# gluecksrad.net
KiCad netlist of a schematic drawn in EAGLE
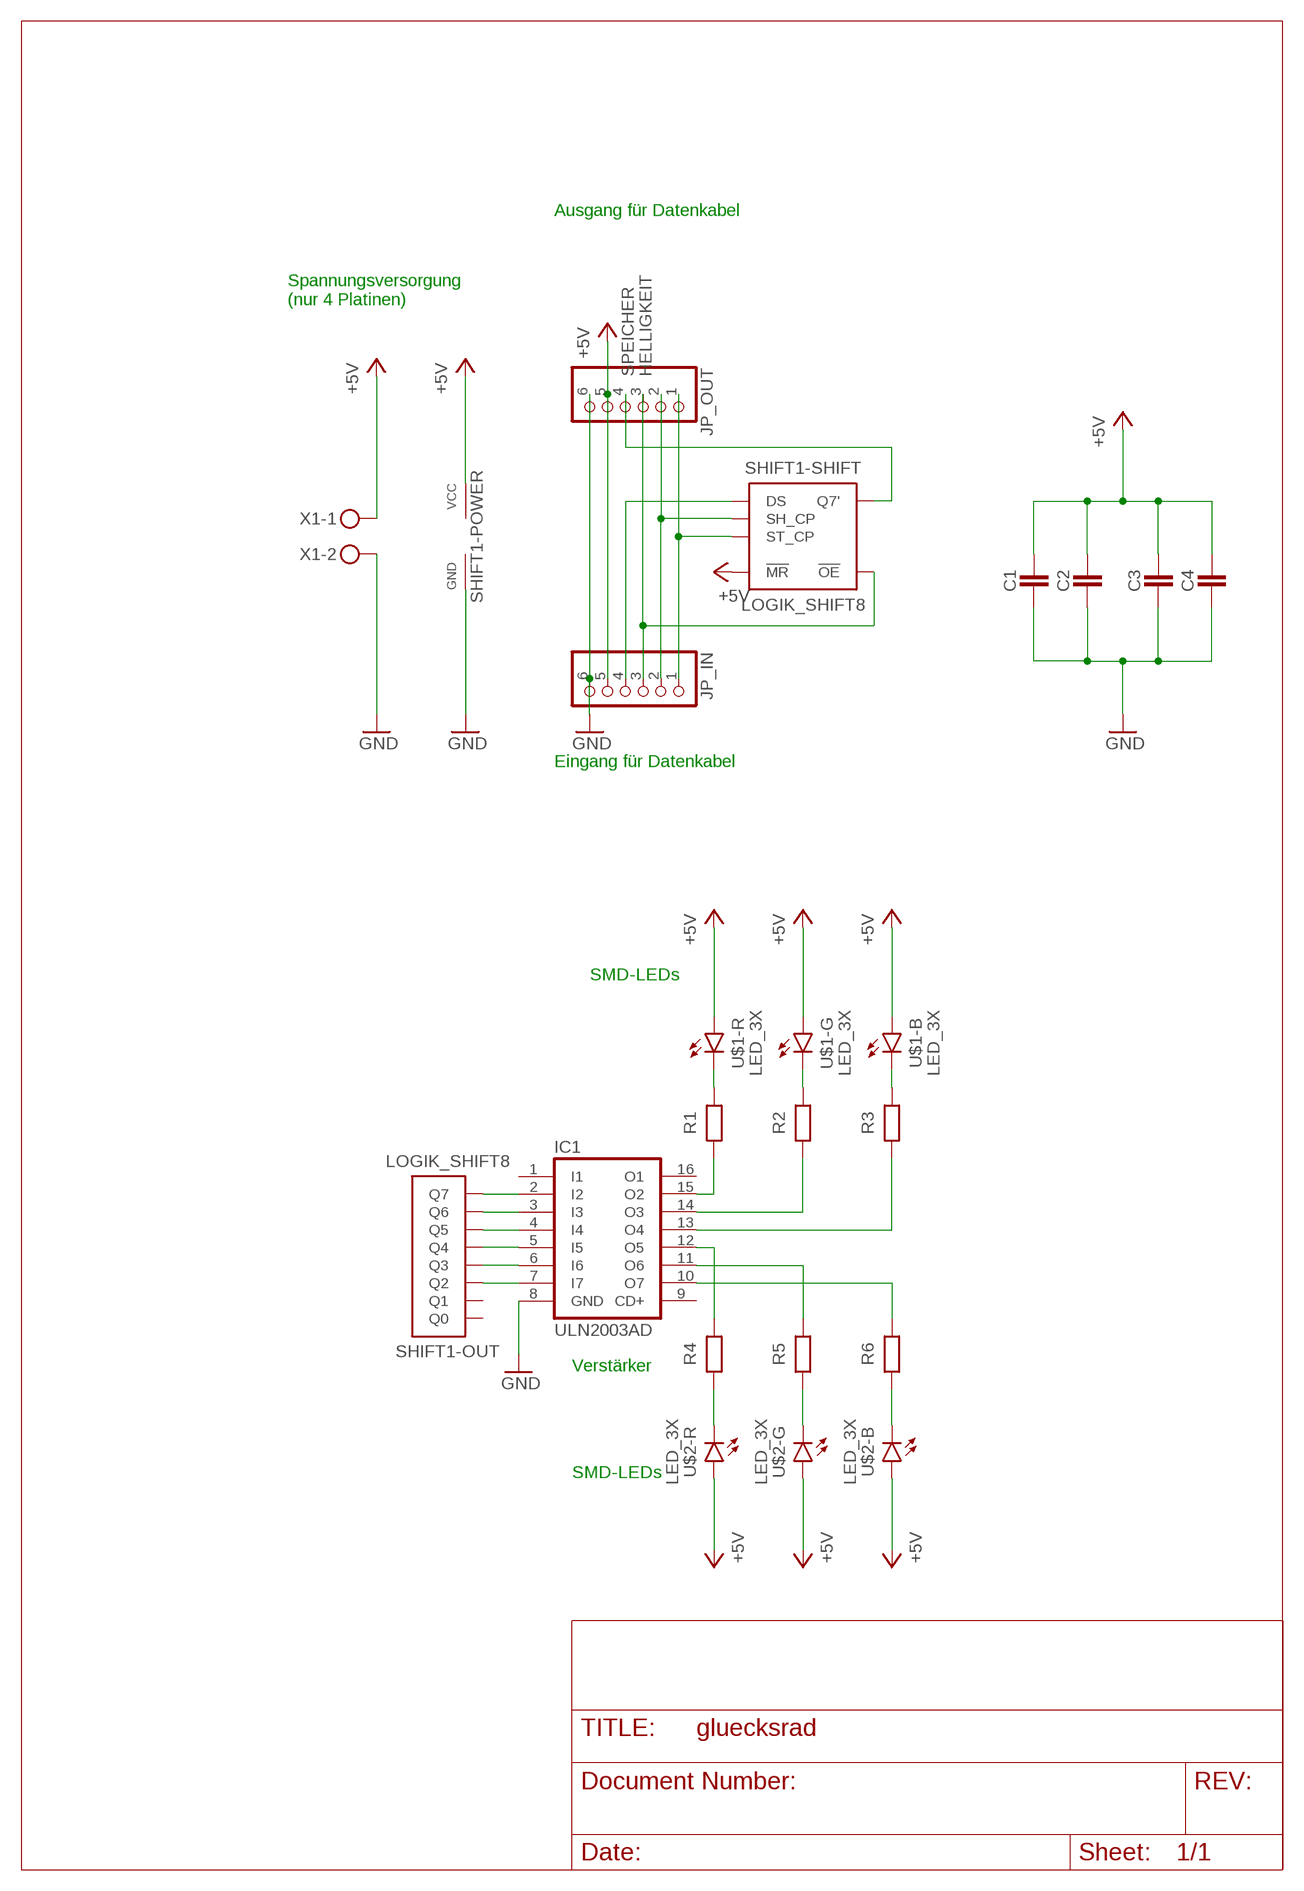
[diagram p0: schematic, sheet 1]

(export (version "E")
  (design (tool "Eeschema 10.0.6"))
  (components
    (comp (ref "C1")
      (value "CAPACITATOR-2,5MM")
      (footprint "eagle-import:C_THT_2")
      (libsource (lib "eagle-import") (part "CAPACITATOR-2,5MM"))
    )
    (comp (ref "C2")
      (value "CAPACITATOR-5MM")
      (footprint "eagle-import:C_THT_3")
      (libsource (lib "eagle-import") (part "CAPACITATOR-5MM"))
    )
    (comp (ref "C3")
      (value "CAPACITATOR-2,5MM")
      (footprint "eagle-import:C_THT_2")
      (libsource (lib "eagle-import") (part "CAPACITATOR-2,5MM"))
    )
    (comp (ref "C4")
      (value "CAPACITATOR-2,5MM")
      (footprint "eagle-import:C_THT_2")
      (libsource (lib "eagle-import") (part "CAPACITATOR-2,5MM"))
    )
    (comp (ref "IC1")
      (value "ULN2003AD")
      (footprint "eagle-import:SO16")
      (libsource (lib "eagle-import") (part "ULN2003AD"))
    )
    (comp (ref "JP_IN")
      (value "PINHD-1X6/90")
      (footprint "eagle-import:1X06_90")
      (libsource (lib "eagle-import") (part "PINHD-1X6/90"))
    )
    (comp (ref "JP_OUT")
      (value "PINHD-1X6/90")
      (footprint "eagle-import:1X06_90")
      (libsource (lib "eagle-import") (part "PINHD-1X6/90"))
    )
    (comp (ref "R1")
      (value "RESISTOR-10MM")
      (footprint "eagle-import:R_THT_4")
      (libsource (lib "eagle-import") (part "RESISTOR-10MM"))
    )
    (comp (ref "R2")
      (value "RESISTOR-10MM")
      (footprint "eagle-import:R_THT_4")
      (libsource (lib "eagle-import") (part "RESISTOR-10MM"))
    )
    (comp (ref "R3")
      (value "RESISTOR-10MM")
      (footprint "eagle-import:R_THT_4")
      (libsource (lib "eagle-import") (part "RESISTOR-10MM"))
    )
    (comp (ref "R4")
      (value "RESISTOR-10MM")
      (footprint "eagle-import:R_THT_4")
      (libsource (lib "eagle-import") (part "RESISTOR-10MM"))
    )
    (comp (ref "R5")
      (value "RESISTOR-10MM")
      (footprint "eagle-import:R_THT_4")
      (libsource (lib "eagle-import") (part "RESISTOR-10MM"))
    )
    (comp (ref "R6")
      (value "RESISTOR-10MM")
      (footprint "eagle-import:R_THT_4")
      (libsource (lib "eagle-import") (part "RESISTOR-10MM"))
    )
    (comp (ref "SHIFT1")
      (value "LOGIK_SHIFT8")
      (footprint "eagle-import:IC_SOIC16")
      (libsource (lib "eagle-import") (part "LOGIK_SHIFT8"))
    )
    (comp (ref "U$1")
      (value "LED_3X")
      (footprint "eagle-import:LED_TOP_PLCC6")
      (libsource (lib "eagle-import") (part "LED_3X"))
    )
    (comp (ref "U$2")
      (value "LED_3X")
      (footprint "eagle-import:LED_TOP_PLCC6")
      (libsource (lib "eagle-import") (part "LED_3X"))
    )
    (comp (ref "X1")
      (value "STECKER_SPG_2")
      (footprint "eagle-import:STECKER_SPG_2")
      (libsource (lib "eagle-import") (part "STECKER_SPG_2"))
    )
  )
  (nets
    (net (code "1") (name "+5V") (class "Default")
      (node (ref "C1") (pin "1") (pinfunction "1_1") (pintype "passive"))
      (node (ref "C2") (pin "1") (pinfunction "1_1") (pintype "passive"))
      (node (ref "C3") (pin "1") (pinfunction "1_1") (pintype "passive"))
      (node (ref "C4") (pin "1") (pinfunction "1_1") (pintype "passive"))
      (node (ref "JP_IN") (pin "5") (pinfunction "5_5") (pintype "passive"))
      (node (ref "JP_OUT") (pin "5") (pinfunction "5_5") (pintype "passive"))
      (node (ref "SHIFT1") (pin "P$10") (pinfunction "~{MR}_P$10") (pintype "input"))
      (node (ref "SHIFT1") (pin "P$16") (pinfunction "VCC_P$16") (pintype "power_in"))
      (node (ref "U$1") (pin "1") (pinfunction "A_1") (pintype "passive"))
      (node (ref "U$1") (pin "3") (pinfunction "A_3") (pintype "passive"))
      (node (ref "U$1") (pin "4") (pinfunction "A_4") (pintype "passive"))
      (node (ref "U$2") (pin "1") (pinfunction "A_1") (pintype "passive"))
      (node (ref "U$2") (pin "3") (pinfunction "A_3") (pintype "passive"))
      (node (ref "U$2") (pin "4") (pinfunction "A_4") (pintype "passive"))
      (node (ref "X1") (pin "1") (pinfunction "KL_1") (pintype "passive"))
    )
    (net (code "2") (name "/HELLIGKEIT") (class "Default")
      (node (ref "JP_IN") (pin "3") (pinfunction "3_3") (pintype "passive"))
      (node (ref "JP_OUT") (pin "3") (pinfunction "3_3") (pintype "passive"))
      (node (ref "SHIFT1") (pin "P$13") (pinfunction "~{OE}_P$13") (pintype "input"))
    )
    (net (code "3") (name "/SPEICHER") (class "Default")
      (node (ref "JP_IN") (pin "1") (pinfunction "1_1") (pintype "passive"))
      (node (ref "JP_OUT") (pin "1") (pinfunction "1_1") (pintype "passive"))
      (node (ref "SHIFT1") (pin "P$12") (pinfunction "ST_CP_P$12") (pintype "input"))
    )
    (net (code "4") (name "GND") (class "Default")
      (node (ref "C1") (pin "2") (pinfunction "2_2") (pintype "passive"))
      (node (ref "C2") (pin "2") (pinfunction "2_2") (pintype "passive"))
      (node (ref "C3") (pin "2") (pinfunction "2_2") (pintype "passive"))
      (node (ref "C4") (pin "2") (pinfunction "2_2") (pintype "passive"))
      (node (ref "IC1") (pin "8") (pinfunction "GND_8") (pintype "power_in"))
      (node (ref "JP_IN") (pin "6") (pinfunction "6_6") (pintype "passive"))
      (node (ref "JP_OUT") (pin "6") (pinfunction "6_6") (pintype "passive"))
      (node (ref "SHIFT1") (pin "P$8") (pinfunction "GND_P$8") (pintype "power_in"))
      (node (ref "X1") (pin "2") (pinfunction "KL_2") (pintype "passive"))
    )
    (net (code "5") (name "Net-(IC1-I2)") (class "Default")
      (node (ref "IC1") (pin "2") (pinfunction "I2_2") (pintype "input"))
      (node (ref "SHIFT1") (pin "P$7") (pinfunction "Q7_P$7") (pintype "output"))
    )
    (net (code "6") (name "Net-(IC1-I3)") (class "Default")
      (node (ref "IC1") (pin "3") (pinfunction "I3_3") (pintype "input"))
      (node (ref "SHIFT1") (pin "P$6") (pinfunction "Q6_P$6") (pintype "output"))
    )
    (net (code "7") (name "Net-(IC1-I4)") (class "Default")
      (node (ref "IC1") (pin "4") (pinfunction "I4_4") (pintype "input"))
      (node (ref "SHIFT1") (pin "P$5") (pinfunction "Q5_P$5") (pintype "output"))
    )
    (net (code "8") (name "Net-(IC1-I5)") (class "Default")
      (node (ref "IC1") (pin "5") (pinfunction "I5_5") (pintype "input"))
      (node (ref "SHIFT1") (pin "P$4") (pinfunction "Q4_P$4") (pintype "output"))
    )
    (net (code "9") (name "Net-(IC1-I6)") (class "Default")
      (node (ref "IC1") (pin "6") (pinfunction "I6_6") (pintype "input"))
      (node (ref "SHIFT1") (pin "P$3") (pinfunction "Q3_P$3") (pintype "output"))
    )
    (net (code "10") (name "Net-(IC1-I7)") (class "Default")
      (node (ref "IC1") (pin "7") (pinfunction "I7_7") (pintype "input"))
      (node (ref "SHIFT1") (pin "P$2") (pinfunction "Q2_P$2") (pintype "output"))
    )
    (net (code "11") (name "Net-(IC1-O2)") (class "Default")
      (node (ref "IC1") (pin "15") (pinfunction "O2_15") (pintype "open_collector"))
      (node (ref "R1") (pin "2") (pinfunction "P2_2") (pintype "passive"))
    )
    (net (code "12") (name "Net-(IC1-O3)") (class "Default")
      (node (ref "IC1") (pin "14") (pinfunction "O3_14") (pintype "open_collector"))
      (node (ref "R2") (pin "2") (pinfunction "P2_2") (pintype "passive"))
    )
    (net (code "13") (name "Net-(IC1-O4)") (class "Default")
      (node (ref "IC1") (pin "13") (pinfunction "O4_13") (pintype "open_collector"))
      (node (ref "R3") (pin "2") (pinfunction "P2_2") (pintype "passive"))
    )
    (net (code "14") (name "Net-(IC1-O5)") (class "Default")
      (node (ref "IC1") (pin "12") (pinfunction "O5_12") (pintype "open_collector"))
      (node (ref "R4") (pin "1") (pinfunction "P1_1") (pintype "passive"))
    )
    (net (code "15") (name "Net-(IC1-O6)") (class "Default")
      (node (ref "IC1") (pin "11") (pinfunction "O6_11") (pintype "open_collector"))
      (node (ref "R5") (pin "1") (pinfunction "P1_1") (pintype "passive"))
    )
    (net (code "16") (name "Net-(IC1-O7)") (class "Default")
      (node (ref "IC1") (pin "10") (pinfunction "O7_10") (pintype "open_collector"))
      (node (ref "R6") (pin "1") (pinfunction "P1_1") (pintype "passive"))
    )
    (net (code "17") (name "Net-(R1-P1)") (class "Default")
      (node (ref "R1") (pin "1") (pinfunction "P1_1") (pintype "passive"))
      (node (ref "U$1") (pin "6") (pinfunction "C_6") (pintype "passive"))
    )
    (net (code "18") (name "Net-(R2-P1)") (class "Default")
      (node (ref "R2") (pin "1") (pinfunction "P1_1") (pintype "passive"))
      (node (ref "U$1") (pin "2") (pinfunction "C_2") (pintype "passive"))
    )
    (net (code "19") (name "Net-(R3-P1)") (class "Default")
      (node (ref "R3") (pin "1") (pinfunction "P1_1") (pintype "passive"))
      (node (ref "U$1") (pin "5") (pinfunction "C_5") (pintype "passive"))
    )
    (net (code "20") (name "Net-(R4-P2)") (class "Default")
      (node (ref "R4") (pin "2") (pinfunction "P2_2") (pintype "passive"))
      (node (ref "U$2") (pin "6") (pinfunction "C_6") (pintype "passive"))
    )
    (net (code "21") (name "Net-(R5-P2)") (class "Default")
      (node (ref "R5") (pin "2") (pinfunction "P2_2") (pintype "passive"))
      (node (ref "U$2") (pin "2") (pinfunction "C_2") (pintype "passive"))
    )
    (net (code "22") (name "Net-(R6-P2)") (class "Default")
      (node (ref "R6") (pin "2") (pinfunction "P2_2") (pintype "passive"))
      (node (ref "U$2") (pin "5") (pinfunction "C_5") (pintype "passive"))
    )
    (net (code "23") (name "Net-(SHIFT1C-DS)") (class "Default")
      (node (ref "JP_IN") (pin "4") (pinfunction "4_4") (pintype "passive"))
      (node (ref "SHIFT1") (pin "P$14") (pinfunction "DS_P$14") (pintype "input"))
    )
    (net (code "24") (name "Net-(SHIFT1C-Q7')") (class "Default")
      (node (ref "JP_OUT") (pin "4") (pinfunction "4_4") (pintype "passive"))
      (node (ref "SHIFT1") (pin "P$9") (pinfunction "Q7'_P$9") (pintype "output"))
    )
    (net (code "25") (name "Net-(SHIFT1C-SH_CP)") (class "Default")
      (node (ref "JP_IN") (pin "2") (pinfunction "2_2") (pintype "passive"))
      (node (ref "JP_OUT") (pin "2") (pinfunction "2_2") (pintype "passive"))
      (node (ref "SHIFT1") (pin "P$11") (pinfunction "SH_CP_P$11") (pintype "input"))
    )
    (net (code "26") (name "unconnected-(IC1-CD+-Pad9)") (class "Default")
      (node (ref "IC1") (pin "9") (pinfunction "CD+_9") (pintype "passive"))
    )
    (net (code "27") (name "unconnected-(IC1-I1-Pad1)") (class "Default")
      (node (ref "IC1") (pin "1") (pinfunction "I1_1") (pintype "input"))
    )
    (net (code "28") (name "unconnected-(IC1-O1-Pad16)") (class "Default")
      (node (ref "IC1") (pin "16") (pinfunction "O1_16") (pintype "open_collector"))
    )
    (net (code "29") (name "unconnected-(SHIFT1A-Q0-PadP$15)") (class "Default")
      (node (ref "SHIFT1") (pin "P$15") (pinfunction "Q0_P$15") (pintype "output"))
    )
    (net (code "30") (name "unconnected-(SHIFT1A-Q1-PadP$1)") (class "Default")
      (node (ref "SHIFT1") (pin "P$1") (pinfunction "Q1_P$1") (pintype "output"))
    )
  )
)
